# PowerInput.net
KiCad netlist of a schematic drawn in Altium Designer
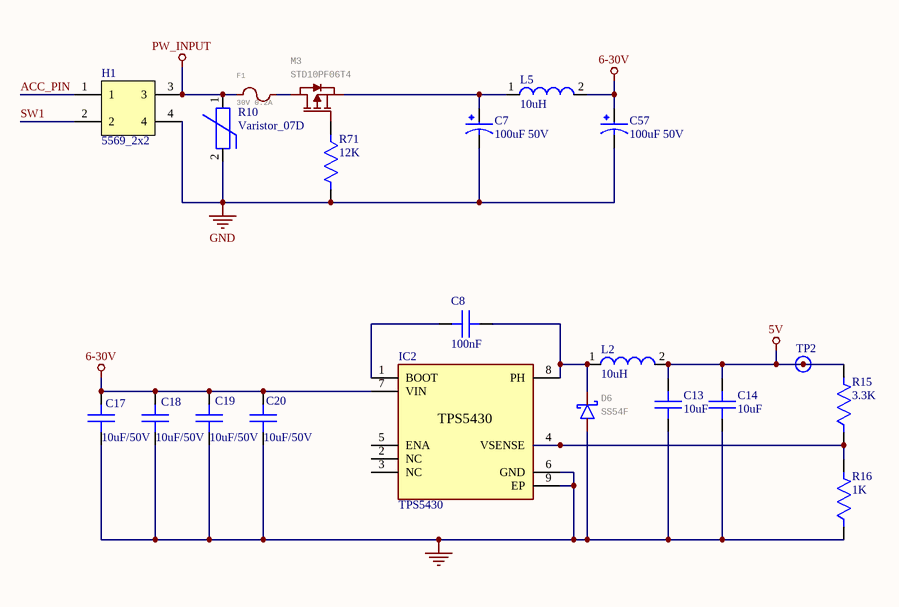
[diagram p0: PowerInput.SchDoc]

(export (version "E")
  (design (tool "Eeschema 10.0.6"))
  (components
    (comp (ref "C7")
      (value "100uF 50V")
      (footprint "CAP_AL_8x12.5")
      (description "Aluminum Electrolytic Capacitors - Radial Leaded 50VDC 1200uF 10000H 16x25mm")
      (fields (field (name "MF") "Panasonic") (field (name "MP") "EEU-FS1H122"))
      (libsource (lib "UY_Schlib") (part "CAP_AL_8x12.5"))
    )
    (comp (ref "C8") (value "100nF") (footprint "C0603") (libsource (lib "UY_Schlib") (part "Capacitor")))
    (comp (ref "C13")
      (value "10uF")
      (footprint "C0805")
      (libsource (lib "UY_Schlib") (part "Capacitor 0805"))
    )
    (comp (ref "C14")
      (value "10uF")
      (footprint "C0805")
      (libsource (lib "UY_Schlib") (part "Capacitor 0805"))
    )
    (comp (ref "C17")
      (value "10uF/50V")
      (footprint "C0805")
      (libsource (lib "UY_Schlib") (part "Capacitor 0805"))
    )
    (comp (ref "C18")
      (value "10uF/50V")
      (footprint "C0805")
      (libsource (lib "UY_Schlib") (part "Capacitor 0805"))
    )
    (comp (ref "C19")
      (value "10uF/50V")
      (footprint "C0805")
      (libsource (lib "UY_Schlib") (part "Capacitor 0805"))
    )
    (comp (ref "C20")
      (value "10uF/50V")
      (footprint "C0805")
      (libsource (lib "UY_Schlib") (part "Capacitor 0805"))
    )
    (comp (ref "C57")
      (value "100uF 50V")
      (footprint "CAP_AL_8x12.5")
      (description "Aluminum Electrolytic Capacitors - Radial Leaded 50VDC 1200uF 10000H 16x25mm")
      (fields (field (name "MF") "Panasonic") (field (name "MP") "EEU-FS1H122"))
      (libsource (lib "UY_Schlib") (part "CAP_AL_8x12.5"))
    )
    (comp (ref "D6") (value "SS54F") (footprint "SMAF") (libsource (lib "UY_Schlib") (part "SS54F")))
    (comp (ref "F1")
      (value "30V 0.2A")
      (footprint "FUSE_MF-MSMF150")
      (fields (field (name "MF") "Bourns") (field (name "MP") "MF-MSMF150"))
      (libsource (lib "UY_Schlib") (part "FUSE_MF-MSMF150"))
    )
    (comp (ref "H1")
      (value "5569_2x2")
      (footprint "5569_2x2")
      (libsource (lib "UY_5569_Header") (part "5569_2x2"))
    )
    (comp (ref "IC2")
      (value "TPS5430")
      (footprint "SOIC-8E")
      (description "Buck Step-Down Converter\r\n(5.5V to 36V Input, 3A)")
      (fields (field (name "MF") "Texas Instruments") (field (name "MP") "TPS5430DDA"))
      (libsource (lib "UY_Schlib") (part "TPS5430"))
    )
    (comp (ref "L2")
      (value "10uH")
      (footprint "L0630")
      (description "HIGH POWER INDUCTOR 1040")
      (fields (field (name "MF") "Wurth Electronics") (field (name "MP") "74437368047"))
      (libsource (lib "UY_Schlib") (part "Inductor 0630"))
    )
    (comp (ref "L5")
      (value "10uH")
      (footprint "L0630")
      (description "HIGH POWER INDUCTOR 1040")
      (fields (field (name "MF") "Wurth Electronics") (field (name "MP") "74437368047"))
      (libsource (lib "UY_Schlib") (part "Inductor 0630"))
    )
    (comp (ref "M3")
      (value "STD10PF06T4")
      (footprint "TO252-3")
      (description "SOT-23")
      (libsource (lib "UY_Schlib") (part "MOSFETP_TO252"))
    )
    (comp (ref "R10")
      (value "Varistor_07D")
      (footprint "Varistor_07D")
      (libsource (lib "UY_Schlib") (part "Varistor_07D"))
    )
    (comp (ref "R15")
      (value "3.3K")
      (footprint "R0603")
      (description "SMD Resistor 0603")
      (fields
        (field (name "MANUFACTURER") "Yageo")
        (field (name "MANUFACTURER PART NUMBER") "RC0603FR-071KL")
      )
      (libsource (lib "UY_Schlib") (part "Resistor 0603"))
    )
    (comp (ref "R16")
      (value "1K")
      (footprint "R0603")
      (description "SMD Resistor 0603")
      (fields
        (field (name "MANUFACTURER") "Yageo")
        (field (name "MANUFACTURER PART NUMBER") "RC0603FR-071KL")
      )
      (libsource (lib "UY_Schlib") (part "Resistor 0603"))
    )
    (comp (ref "R71")
      (value "12K")
      (footprint "R0603")
      (description "SMD Resistor 0603")
      (fields
        (field (name "MANUFACTURER") "Yageo")
        (field (name "MANUFACTURER PART NUMBER") "RC0603FR-071KL")
      )
      (libsource (lib "UY_Schlib") (part "Resistor 0603"))
    )
    (comp (ref "TP2")
      (value "TestPoint_1MM")
      (footprint "TestPoint_1MM")
      (libsource (lib "UY_Schlib") (part "TestPoint_1MM"))
    )
  )
  (nets
    (net (code "1") (name "/ACC_PIN") (class "Default")
      (node (ref "H1") (pin "1") (pinfunction "1_1") (pintype "passive"))
    )
    (net (code "2") (name "/SW1") (class "Default")
      (node (ref "H1") (pin "2") (pinfunction "2_2") (pintype "passive"))
    )
    (net (code "3") (name "5V") (class "Default")
      (node (ref "C13") (pin "1") (pinfunction "1_1") (pintype "passive"))
      (node (ref "C14") (pin "1") (pinfunction "1_1") (pintype "passive"))
      (node (ref "L2") (pin "2") (pinfunction "2_2") (pintype "passive"))
      (node (ref "R15") (pin "2") (pinfunction "2_2") (pintype "passive"))
      (node (ref "TP2") (pin "1") (pinfunction "1_1") (pintype "passive"))
    )
    (net (code "4") (name "6-30V") (class "Default")
      (node (ref "C17") (pin "1") (pinfunction "1_1") (pintype "passive"))
      (node (ref "C18") (pin "1") (pinfunction "1_1") (pintype "passive"))
      (node (ref "C19") (pin "1") (pinfunction "1_1") (pintype "passive"))
      (node (ref "C20") (pin "1") (pinfunction "1_1") (pintype "passive"))
      (node (ref "C57") (pin "1") (pinfunction "1_1") (pintype "passive"))
      (node (ref "IC2") (pin "7") (pinfunction "VIN_7") (pintype "passive"))
      (node (ref "L5") (pin "2") (pinfunction "2_2") (pintype "passive"))
    )
    (net (code "5") (name "GND") (class "Default")
      (node (ref "C13") (pin "2") (pinfunction "2_2") (pintype "passive"))
      (node (ref "C14") (pin "2") (pinfunction "2_2") (pintype "passive"))
      (node (ref "C17") (pin "2") (pinfunction "2_2") (pintype "passive"))
      (node (ref "C18") (pin "2") (pinfunction "2_2") (pintype "passive"))
      (node (ref "C19") (pin "2") (pinfunction "2_2") (pintype "passive"))
      (node (ref "C20") (pin "2") (pinfunction "2_2") (pintype "passive"))
      (node (ref "C57") (pin "2") (pinfunction "2_2") (pintype "passive"))
      (node (ref "C7") (pin "2") (pinfunction "2_2") (pintype "passive"))
      (node (ref "D6") (pin "A") (pinfunction "A_A") (pintype "passive"))
      (node (ref "H1") (pin "4") (pinfunction "4_4") (pintype "passive"))
      (node (ref "IC2") (pin "6") (pinfunction "GND_6") (pintype "passive"))
      (node (ref "IC2") (pin "9") (pinfunction "EP_9") (pintype "passive"))
      (node (ref "R10") (pin "2") (pinfunction "2_2") (pintype "passive"))
      (node (ref "R16") (pin "1") (pinfunction "1_1") (pintype "passive"))
      (node (ref "R71") (pin "2") (pinfunction "2_2") (pintype "passive"))
    )
    (net (code "6") (name "Net-(IC2-BOOT)") (class "Default")
      (node (ref "C8") (pin "1") (pinfunction "1_1") (pintype "passive"))
      (node (ref "IC2") (pin "1") (pinfunction "BOOT_1") (pintype "passive"))
    )
    (net (code "7") (name "Net-(IC2-PH)") (class "Default")
      (node (ref "C8") (pin "2") (pinfunction "2_2") (pintype "passive"))
      (node (ref "D6") (pin "C") (pinfunction "C_C") (pintype "passive"))
      (node (ref "IC2") (pin "8") (pinfunction "PH_8") (pintype "passive"))
      (node (ref "L2") (pin "1") (pinfunction "1_1") (pintype "passive"))
    )
    (net (code "8") (name "Net-(IC2-VSENSE)") (class "Default")
      (node (ref "IC2") (pin "4") (pinfunction "VSENSE_4") (pintype "passive"))
      (node (ref "R15") (pin "1") (pinfunction "1_1") (pintype "passive"))
      (node (ref "R16") (pin "2") (pinfunction "2_2") (pintype "passive"))
    )
    (net (code "9") (name "Net-(M3-D)") (class "Default")
      (node (ref "F1") (pin "2") (pinfunction "2_2") (pintype "passive"))
      (node (ref "M3") (pin "3") (pinfunction "D_3") (pintype "passive"))
    )
    (net (code "10") (name "Net-(M3-G)") (class "Default")
      (node (ref "M3") (pin "1") (pinfunction "G_1") (pintype "passive"))
      (node (ref "R71") (pin "1") (pinfunction "1_1") (pintype "passive"))
    )
    (net (code "11") (name "Net-(M3-S)") (class "Default")
      (node (ref "C7") (pin "1") (pinfunction "1_1") (pintype "passive"))
      (node (ref "L5") (pin "1") (pinfunction "1_1") (pintype "passive"))
      (node (ref "M3") (pin "2") (pinfunction "S_2") (pintype "passive"))
    )
    (net (code "12") (name "PW_INPUT") (class "Default")
      (node (ref "F1") (pin "1") (pinfunction "1_1") (pintype "passive"))
      (node (ref "H1") (pin "3") (pinfunction "3_3") (pintype "passive"))
      (node (ref "R10") (pin "1") (pinfunction "1_1") (pintype "passive"))
    )
    (net (code "13") (name "unconnected-(IC2-ENA-Pad5)") (class "Default")
      (node (ref "IC2") (pin "5") (pinfunction "ENA_5") (pintype "passive"))
    )
    (net (code "14") (name "unconnected-(IC2-NC-Pad2)") (class "Default")
      (node (ref "IC2") (pin "2") (pinfunction "NC_2") (pintype "passive"))
    )
    (net (code "15") (name "unconnected-(IC2-NC-Pad3)") (class "Default")
      (node (ref "IC2") (pin "3") (pinfunction "NC_3") (pintype "passive"))
    )
  )
)
